# Arbol-Iot_V1-0.net
KiCad netlist of a schematic drawn in EAGLE
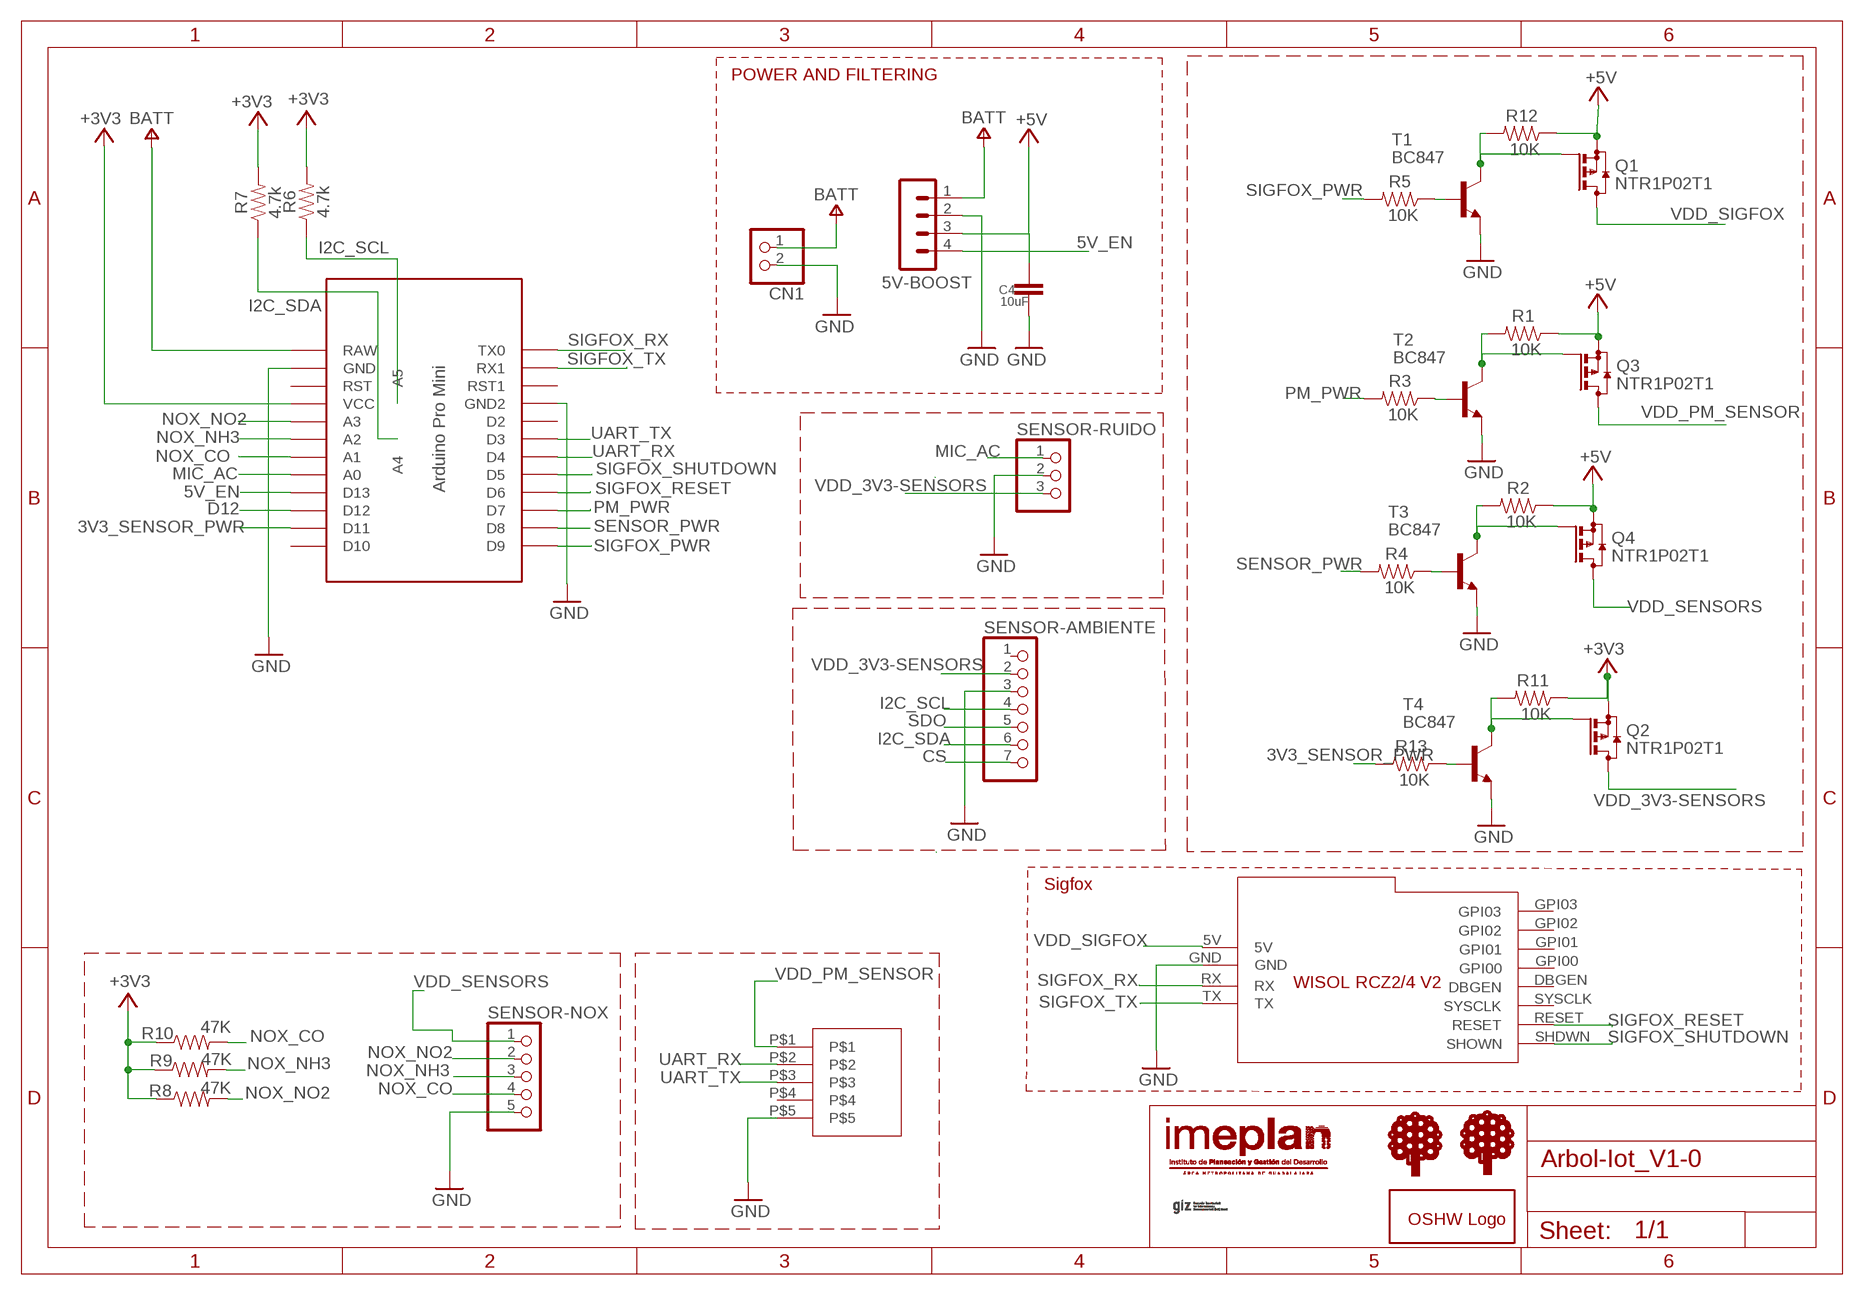
[diagram p0: schematic, sheet 1]

(export (version "E")
  (design (tool "Eeschema 10.0.6"))
  (components
    (comp (ref "5V-BOOST")
      (value "MA04-1")
      (footprint "eagle-import:MA04-1")
      (libsource (lib "eagle-import") (part "MA04-1"))
    )
    (comp (ref "C4")
      (value "10uF")
      (footprint "eagle-import:C1206")
      (libsource (lib "eagle-import") (part "C-EUC1206"))
    )
    (comp (ref "CN1")
      (value "JST_2PIN-SMT-RA")
      (footprint "eagle-import:JST-PH-2-SMT-RA")
      (libsource (lib "eagle-import") (part "JST_2PIN-SMT-RA"))
    )
    (comp (ref "GOLD_ORB_SM1")
      (value "OSHWLOGOLOGO5MM")
      (footprint "eagle-import:OSHW_5MM")
      (libsource (lib "eagle-import") (part "OSHWLOGOLOGO5MM"))
    )
    (comp (ref "PM-SENSOR")
      (value "S5B-ZR-3.4")
      (footprint "eagle-import:S5B-ZR-3.4")
      (libsource (lib "eagle-import") (part "S5B-ZR-3.4"))
    )
    (comp (ref "Q1")
      (value "NTR1P02T1")
      (footprint "eagle-import:SOT23")
      (libsource (lib "eagle-import") (part "BSS84"))
    )
    (comp (ref "Q2")
      (value "NTR1P02T1")
      (footprint "eagle-import:SOT23")
      (libsource (lib "eagle-import") (part "BSS84"))
    )
    (comp (ref "Q3")
      (value "NTR1P02T1")
      (footprint "eagle-import:SOT23")
      (libsource (lib "eagle-import") (part "BSS84"))
    )
    (comp (ref "Q4")
      (value "NTR1P02T1")
      (footprint "eagle-import:SOT23")
      (libsource (lib "eagle-import") (part "BSS84"))
    )
    (comp (ref "R1")
      (value "10K")
      (footprint "eagle-import:1206")
      (libsource (lib "eagle-import") (part "10OHM-1206-1/4W-1%"))
    )
    (comp (ref "R2")
      (value "10K")
      (footprint "eagle-import:1206")
      (libsource (lib "eagle-import") (part "10OHM-1206-1/4W-1%"))
    )
    (comp (ref "R3")
      (value "10K")
      (footprint "eagle-import:1206")
      (libsource (lib "eagle-import") (part "10OHM-1206-1/4W-1%"))
    )
    (comp (ref "R4")
      (value "10K")
      (footprint "eagle-import:1206")
      (libsource (lib "eagle-import") (part "10OHM-1206-1/4W-1%"))
    )
    (comp (ref "R5")
      (value "10K")
      (footprint "eagle-import:1206")
      (libsource (lib "eagle-import") (part "10OHM-1206-1/4W-1%"))
    )
    (comp (ref "R6")
      (value "4.7k")
      (footprint "eagle-import:1206")
      (libsource (lib "eagle-import") (part "10OHM-1206-1/4W-1%"))
    )
    (comp (ref "R7")
      (value "4.7k")
      (footprint "eagle-import:1206")
      (libsource (lib "eagle-import") (part "10OHM-1206-1/4W-1%"))
    )
    (comp (ref "R8")
      (value "47K")
      (footprint "eagle-import:1206")
      (libsource (lib "eagle-import") (part "10OHM-1206-1/4W-1%"))
    )
    (comp (ref "R9")
      (value "47K")
      (footprint "eagle-import:1206")
      (libsource (lib "eagle-import") (part "10OHM-1206-1/4W-1%"))
    )
    (comp (ref "R10")
      (value "47K")
      (footprint "eagle-import:1206")
      (libsource (lib "eagle-import") (part "10OHM-1206-1/4W-1%"))
    )
    (comp (ref "R11")
      (value "10K")
      (footprint "eagle-import:1206")
      (libsource (lib "eagle-import") (part "10OHM-1206-1/4W-1%"))
    )
    (comp (ref "R12")
      (value "10K")
      (footprint "eagle-import:1206")
      (libsource (lib "eagle-import") (part "10OHM-1206-1/4W-1%"))
    )
    (comp (ref "R13")
      (value "10K")
      (footprint "eagle-import:1206")
      (libsource (lib "eagle-import") (part "10OHM-1206-1/4W-1%"))
    )
    (comp (ref "SENSOR-AMBIENTE")
      (value "PINHD-1X7")
      (footprint "eagle-import:1X07")
      (libsource (lib "eagle-import") (part "PINHD-1X7"))
    )
    (comp (ref "SENSOR-NOX")
      (value "PINHD-1X5")
      (footprint "eagle-import:1X05")
      (libsource (lib "eagle-import") (part "PINHD-1X5"))
    )
    (comp (ref "SENSOR-RUIDO")
      (value "PINHD-1X3")
      (footprint "eagle-import:1X03")
      (libsource (lib "eagle-import") (part "PINHD-1X3"))
    )
    (comp (ref "T1")
      (value "BC847")
      (footprint "eagle-import:SOT23")
      (libsource (lib "eagle-import") (part "BC847"))
    )
    (comp (ref "T2")
      (value "BC847")
      (footprint "eagle-import:SOT23")
      (libsource (lib "eagle-import") (part "BC847"))
    )
    (comp (ref "T3")
      (value "BC847")
      (footprint "eagle-import:SOT23")
      (libsource (lib "eagle-import") (part "BC847"))
    )
    (comp (ref "T4")
      (value "BC847")
      (footprint "eagle-import:SOT23")
      (libsource (lib "eagle-import") (part "BC847"))
    )
    (comp (ref "U$1")
      (value "GIZ-LOGO")
      (footprint "eagle-import:GIZ-LOGO")
      (libsource (lib "eagle-import") (part "GIZ-LOGO"))
    )
    (comp (ref "U$2")
      (value "WISOL-RCZ2/4V2")
      (footprint "eagle-import:BREAKOUT-WISOL-SIGFOX")
      (libsource (lib "eagle-import") (part "WISOL-RCZ2/4V2"))
    )
    (comp (ref "U$3")
      (value "ARBOL-IOT-LETRAS")
      (footprint "eagle-import:ARBOL-IOT-LETRAS")
      (libsource (lib "eagle-import") (part "ARBOL-IOT-LETRAS"))
    )
    (comp (ref "U$4")
      (value "BAST")
      (footprint "eagle-import:BAST")
      (libsource (lib "eagle-import") (part "BAST"))
    )
    (comp (ref "U$6")
      (value "ARBOL-IOT-LETRAS")
      (footprint "eagle-import:ARBOL-IOT-LETRAS")
      (libsource (lib "eagle-import") (part "ARBOL-IOT-LETRAS"))
    )
    (comp (ref "U$7")
      (value "IMEPLAN-LOGO")
      (footprint "eagle-import:IMEPLAN-LOGO")
      (libsource (lib "eagle-import") (part "IMEPLAN-LOGO"))
    )
  )
  (nets
    (net (code "1") (name "+3V3") (class "Default")
      (node (ref "Q2") (pin "2") (pinfunction "S_2") (pintype "passive"))
      (node (ref "R10") (pin "1") (pinfunction "1_1") (pintype "passive"))
      (node (ref "R11") (pin "1") (pinfunction "1_1") (pintype "passive"))
      (node (ref "R6") (pin "2") (pinfunction "2_2") (pintype "passive"))
      (node (ref "R7") (pin "2") (pinfunction "2_2") (pintype "passive"))
      (node (ref "R8") (pin "1") (pinfunction "1_1") (pintype "passive"))
      (node (ref "R9") (pin "1") (pinfunction "1_1") (pintype "passive"))
      (node (ref "U$4") (pin "VCC") (pinfunction "VCC_VCC") (pintype "bidirectional"))
    )
    (net (code "2") (name "+5V") (class "Default")
      (node (ref "5V-BOOST") (pin "3") (pinfunction "3_3") (pintype "passive"))
      (node (ref "C4") (pin "1") (pinfunction "1_1") (pintype "passive"))
      (node (ref "Q1") (pin "2") (pinfunction "S_2") (pintype "passive"))
      (node (ref "Q3") (pin "2") (pinfunction "S_2") (pintype "passive"))
      (node (ref "Q4") (pin "2") (pinfunction "S_2") (pintype "passive"))
      (node (ref "R1") (pin "1") (pinfunction "1_1") (pintype "passive"))
      (node (ref "R12") (pin "1") (pinfunction "1_1") (pintype "passive"))
      (node (ref "R2") (pin "1") (pinfunction "1_1") (pintype "passive"))
    )
    (net (code "3") (name "/3V3_SENSOR_PWR") (class "Default")
      (node (ref "R13") (pin "2") (pinfunction "2_2") (pintype "passive"))
      (node (ref "U$4") (pin "D11") (pinfunction "D11_D11") (pintype "bidirectional"))
    )
    (net (code "4") (name "/5V_EN") (class "Default")
      (node (ref "5V-BOOST") (pin "4") (pinfunction "4_4") (pintype "passive"))
      (node (ref "U$4") (pin "D13") (pinfunction "D13_D13") (pintype "bidirectional"))
    )
    (net (code "5") (name "/CS") (class "Default")
      (node (ref "SENSOR-AMBIENTE") (pin "7") (pinfunction "7_7") (pintype "passive"))
    )
    (net (code "6") (name "/D12") (class "Default")
      (node (ref "U$4") (pin "D12") (pinfunction "D12_D12") (pintype "bidirectional"))
    )
    (net (code "7") (name "/I2C_SCL") (class "Default")
      (node (ref "R6") (pin "1") (pinfunction "1_1") (pintype "passive"))
      (node (ref "SENSOR-AMBIENTE") (pin "4") (pinfunction "4_4") (pintype "passive"))
      (node (ref "U$4") (pin "A5") (pinfunction "A5_A5") (pintype "bidirectional"))
    )
    (net (code "8") (name "/I2C_SDA") (class "Default")
      (node (ref "R7") (pin "1") (pinfunction "1_1") (pintype "passive"))
      (node (ref "SENSOR-AMBIENTE") (pin "6") (pinfunction "6_6") (pintype "passive"))
      (node (ref "U$4") (pin "A4") (pinfunction "A4_A4") (pintype "bidirectional"))
    )
    (net (code "9") (name "/MIC_AC") (class "Default")
      (node (ref "SENSOR-RUIDO") (pin "1") (pinfunction "1_1") (pintype "passive"))
      (node (ref "U$4") (pin "A0") (pinfunction "A0_A0") (pintype "bidirectional"))
    )
    (net (code "10") (name "/NOX_CO") (class "Default")
      (node (ref "R10") (pin "2") (pinfunction "2_2") (pintype "passive"))
      (node (ref "SENSOR-NOX") (pin "4") (pinfunction "4_4") (pintype "passive"))
      (node (ref "U$4") (pin "A1") (pinfunction "A1_A1") (pintype "bidirectional"))
    )
    (net (code "11") (name "/NOX_NH3") (class "Default")
      (node (ref "R9") (pin "2") (pinfunction "2_2") (pintype "passive"))
      (node (ref "SENSOR-NOX") (pin "3") (pinfunction "3_3") (pintype "passive"))
      (node (ref "U$4") (pin "A2") (pinfunction "A2_A2") (pintype "bidirectional"))
    )
    (net (code "12") (name "/NOX_NO2") (class "Default")
      (node (ref "R8") (pin "2") (pinfunction "2_2") (pintype "passive"))
      (node (ref "SENSOR-NOX") (pin "2") (pinfunction "2_2") (pintype "passive"))
      (node (ref "U$4") (pin "A3") (pinfunction "A3_A3") (pintype "bidirectional"))
    )
    (net (code "13") (name "/PM_PWR") (class "Default")
      (node (ref "R3") (pin "2") (pinfunction "2_2") (pintype "passive"))
      (node (ref "U$4") (pin "D7") (pinfunction "D7_D7") (pintype "bidirectional"))
    )
    (net (code "14") (name "/SDO") (class "Default")
      (node (ref "SENSOR-AMBIENTE") (pin "5") (pinfunction "5_5") (pintype "passive"))
    )
    (net (code "15") (name "/SENSOR_PWR") (class "Default")
      (node (ref "R4") (pin "2") (pinfunction "2_2") (pintype "passive"))
      (node (ref "U$4") (pin "D8") (pinfunction "D8_D8") (pintype "bidirectional"))
    )
    (net (code "16") (name "/SIGFOX_PWR") (class "Default")
      (node (ref "R5") (pin "2") (pinfunction "2_2") (pintype "passive"))
      (node (ref "U$4") (pin "D9") (pinfunction "D9_D9") (pintype "bidirectional"))
    )
    (net (code "17") (name "/SIGFOX_RESET") (class "Default")
      (node (ref "U$2") (pin "RESET") (pinfunction "RESET_RESET") (pintype "bidirectional"))
      (node (ref "U$4") (pin "D6") (pinfunction "D6_D6") (pintype "bidirectional"))
    )
    (net (code "18") (name "/SIGFOX_RX") (class "Default")
      (node (ref "U$2") (pin "RX") (pinfunction "RX_RX") (pintype "bidirectional"))
      (node (ref "U$4") (pin "TX0") (pinfunction "TX0_TX0") (pintype "bidirectional"))
    )
    (net (code "19") (name "/SIGFOX_SHUTDOWN") (class "Default")
      (node (ref "U$2") (pin "SHDWN") (pinfunction "SHOWN_SHDWN") (pintype "bidirectional"))
      (node (ref "U$4") (pin "D5") (pinfunction "D5_D5") (pintype "bidirectional"))
    )
    (net (code "20") (name "/SIGFOX_TX") (class "Default")
      (node (ref "U$2") (pin "TX") (pinfunction "TX_TX") (pintype "bidirectional"))
      (node (ref "U$4") (pin "RX1") (pinfunction "RX1_RX1") (pintype "bidirectional"))
    )
    (net (code "21") (name "/UART_RX") (class "Default")
      (node (ref "PM-SENSOR") (pin "P$2") (pinfunction "P$2_P$2") (pintype "bidirectional"))
      (node (ref "U$4") (pin "D4") (pinfunction "D4_D4") (pintype "bidirectional"))
    )
    (net (code "22") (name "/UART_TX") (class "Default")
      (node (ref "PM-SENSOR") (pin "P$3") (pinfunction "P$3_P$3") (pintype "bidirectional"))
      (node (ref "U$4") (pin "D3") (pinfunction "D3_D3") (pintype "bidirectional"))
    )
    (net (code "23") (name "/VDD_3V3-SENSORS") (class "Default")
      (node (ref "Q2") (pin "3") (pinfunction "D_3") (pintype "passive"))
      (node (ref "SENSOR-AMBIENTE") (pin "2") (pinfunction "2_2") (pintype "passive"))
      (node (ref "SENSOR-RUIDO") (pin "3") (pinfunction "3_3") (pintype "passive"))
    )
    (net (code "24") (name "/VDD_PM_SENSOR") (class "Default")
      (node (ref "PM-SENSOR") (pin "P$1") (pinfunction "P$1_P$1") (pintype "bidirectional"))
      (node (ref "Q3") (pin "3") (pinfunction "D_3") (pintype "passive"))
    )
    (net (code "25") (name "/VDD_SENSORS") (class "Default")
      (node (ref "Q4") (pin "3") (pinfunction "D_3") (pintype "passive"))
      (node (ref "SENSOR-NOX") (pin "1") (pinfunction "1_1") (pintype "passive"))
    )
    (net (code "26") (name "/VDD_SIGFOX") (class "Default")
      (node (ref "Q1") (pin "3") (pinfunction "D_3") (pintype "passive"))
      (node (ref "U$2") (pin "5V") (pinfunction "5V_5V") (pintype "bidirectional"))
    )
    (net (code "27") (name "BATT") (class "Default")
      (node (ref "5V-BOOST") (pin "1") (pinfunction "1_1") (pintype "passive"))
      (node (ref "CN1") (pin "1") (pinfunction "2_1") (pintype "passive"))
      (node (ref "U$4") (pin "RAW") (pinfunction "RAW_RAW") (pintype "bidirectional"))
    )
    (net (code "28") (name "GND") (class "Default")
      (node (ref "5V-BOOST") (pin "2") (pinfunction "2_2") (pintype "passive"))
      (node (ref "C4") (pin "2") (pinfunction "2_2") (pintype "passive"))
      (node (ref "CN1") (pin "2") (pinfunction "1_2") (pintype "passive"))
      (node (ref "PM-SENSOR") (pin "P$5") (pinfunction "P$5_P$5") (pintype "bidirectional"))
      (node (ref "SENSOR-AMBIENTE") (pin "3") (pinfunction "3_3") (pintype "passive"))
      (node (ref "SENSOR-NOX") (pin "5") (pinfunction "5_5") (pintype "passive"))
      (node (ref "SENSOR-RUIDO") (pin "2") (pinfunction "2_2") (pintype "passive"))
      (node (ref "T1") (pin "2") (pinfunction "E_2") (pintype "passive"))
      (node (ref "T2") (pin "2") (pinfunction "E_2") (pintype "passive"))
      (node (ref "T3") (pin "2") (pinfunction "E_2") (pintype "passive"))
      (node (ref "T4") (pin "2") (pinfunction "E_2") (pintype "passive"))
      (node (ref "U$2") (pin "GND") (pinfunction "GND_GND") (pintype "bidirectional"))
      (node (ref "U$4") (pin "GND") (pinfunction "GND_GND") (pintype "bidirectional"))
      (node (ref "U$4") (pin "GND1") (pinfunction "GND2_GND1") (pintype "bidirectional"))
    )
    (net (code "29") (name "Net-(Q1-G)") (class "Default")
      (node (ref "Q1") (pin "1") (pinfunction "G_1") (pintype "passive"))
      (node (ref "R12") (pin "2") (pinfunction "2_2") (pintype "passive"))
      (node (ref "T1") (pin "3") (pinfunction "C_3") (pintype "passive"))
    )
    (net (code "30") (name "Net-(Q2-G)") (class "Default")
      (node (ref "Q2") (pin "1") (pinfunction "G_1") (pintype "passive"))
      (node (ref "R11") (pin "2") (pinfunction "2_2") (pintype "passive"))
      (node (ref "T4") (pin "3") (pinfunction "C_3") (pintype "passive"))
    )
    (net (code "31") (name "Net-(Q3-G)") (class "Default")
      (node (ref "Q3") (pin "1") (pinfunction "G_1") (pintype "passive"))
      (node (ref "R1") (pin "2") (pinfunction "2_2") (pintype "passive"))
      (node (ref "T2") (pin "3") (pinfunction "C_3") (pintype "passive"))
    )
    (net (code "32") (name "Net-(Q4-G)") (class "Default")
      (node (ref "Q4") (pin "1") (pinfunction "G_1") (pintype "passive"))
      (node (ref "R2") (pin "2") (pinfunction "2_2") (pintype "passive"))
      (node (ref "T3") (pin "3") (pinfunction "C_3") (pintype "passive"))
    )
    (net (code "33") (name "Net-(T1-B)") (class "Default")
      (node (ref "R5") (pin "1") (pinfunction "1_1") (pintype "passive"))
      (node (ref "T1") (pin "1") (pinfunction "B_1") (pintype "passive"))
    )
    (net (code "34") (name "Net-(T2-B)") (class "Default")
      (node (ref "R3") (pin "1") (pinfunction "1_1") (pintype "passive"))
      (node (ref "T2") (pin "1") (pinfunction "B_1") (pintype "passive"))
    )
    (net (code "35") (name "Net-(T3-B)") (class "Default")
      (node (ref "R4") (pin "1") (pinfunction "1_1") (pintype "passive"))
      (node (ref "T3") (pin "1") (pinfunction "B_1") (pintype "passive"))
    )
    (net (code "36") (name "Net-(T4-B)") (class "Default")
      (node (ref "R13") (pin "1") (pinfunction "1_1") (pintype "passive"))
      (node (ref "T4") (pin "1") (pinfunction "B_1") (pintype "passive"))
    )
    (net (code "37") (name "unconnected-(PM-SENSOR-PadP$4)") (class "Default")
      (node (ref "PM-SENSOR") (pin "P$4") (pinfunction "P$4_P$4") (pintype "bidirectional"))
    )
    (net (code "38") (name "unconnected-(SENSOR-AMBIENTE-Pad1)") (class "Default")
      (node (ref "SENSOR-AMBIENTE") (pin "1") (pinfunction "1_1") (pintype "passive"))
    )
    (net (code "39") (name "unconnected-(U$2-PadDBGEN)") (class "Default")
      (node (ref "U$2") (pin "DBGEN") (pinfunction "DBGEN_DBGEN") (pintype "bidirectional"))
    )
    (net (code "40") (name "unconnected-(U$2-PadGPI00)") (class "Default")
      (node (ref "U$2") (pin "GPI00") (pinfunction "GPI00_GPI00") (pintype "bidirectional"))
    )
    (net (code "41") (name "unconnected-(U$2-PadGPI01)") (class "Default")
      (node (ref "U$2") (pin "GPI01") (pinfunction "GPI01_GPI01") (pintype "bidirectional"))
    )
    (net (code "42") (name "unconnected-(U$2-PadGPI02)") (class "Default")
      (node (ref "U$2") (pin "GPI02") (pinfunction "GPI02_GPI02") (pintype "bidirectional"))
    )
    (net (code "43") (name "unconnected-(U$2-PadGPI03)") (class "Default")
      (node (ref "U$2") (pin "GPI03") (pinfunction "GPI03_GPI03") (pintype "bidirectional"))
    )
    (net (code "44") (name "unconnected-(U$2-PadSYSCLK)") (class "Default")
      (node (ref "U$2") (pin "SYSCLK") (pinfunction "SYSCLK_SYSCLK") (pintype "bidirectional"))
    )
    (net (code "45") (name "unconnected-(U$4-PadD2)") (class "Default")
      (node (ref "U$4") (pin "D2") (pinfunction "D2_D2") (pintype "bidirectional"))
    )
    (net (code "46") (name "unconnected-(U$4-PadD10)") (class "Default")
      (node (ref "U$4") (pin "D10") (pinfunction "D10_D10") (pintype "bidirectional"))
    )
    (net (code "47") (name "unconnected-(U$4-PadRST)") (class "Default")
      (node (ref "U$4") (pin "RST") (pinfunction "RST_RST") (pintype "bidirectional"))
    )
    (net (code "48") (name "unconnected-(U$4-PadRST1)") (class "Default")
      (node (ref "U$4") (pin "RST1") (pinfunction "RST1_RST1") (pintype "bidirectional"))
    )
  )
)
